# n.net
KiCad netlist of a schematic drawn in EAGLE
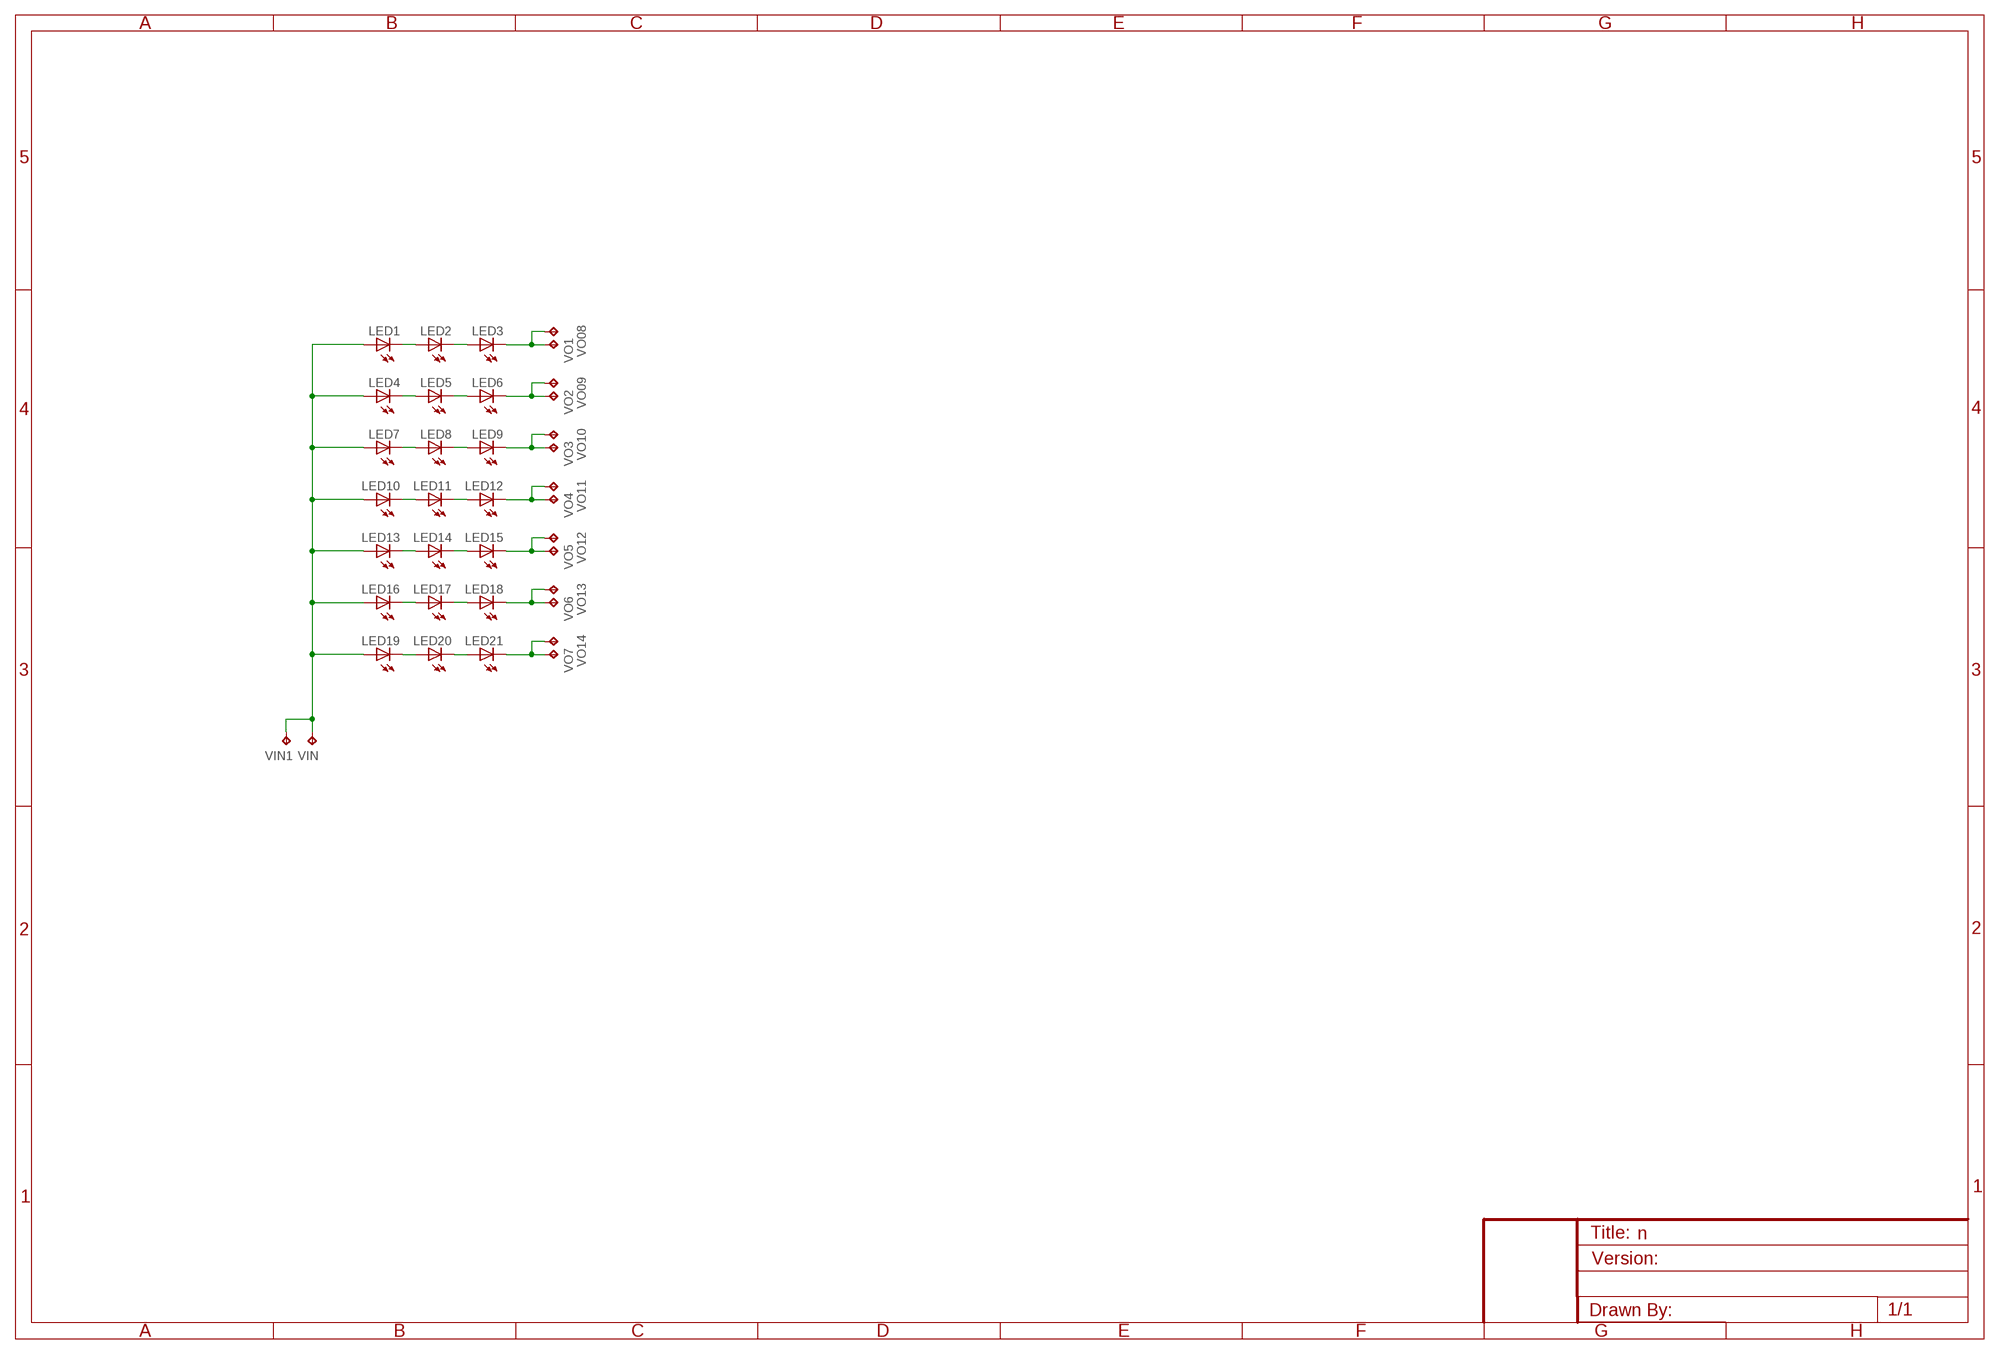
[diagram p0: schematic, sheet 1]

(export (version "E")
  (design (tool "Eeschema 10.0.6"))
  (components
    (comp (ref "LED1")
      (value "LED0805")
      (footprint "eagle-import:LED_0805")
      (libsource (lib "eagle-import") (part "LED0805"))
    )
    (comp (ref "LED2")
      (value "LED0805")
      (footprint "eagle-import:LED_0805")
      (libsource (lib "eagle-import") (part "LED0805"))
    )
    (comp (ref "LED3")
      (value "LED0805")
      (footprint "eagle-import:LED_0805")
      (libsource (lib "eagle-import") (part "LED0805"))
    )
    (comp (ref "LED4")
      (value "LED0805")
      (footprint "eagle-import:LED_0805")
      (libsource (lib "eagle-import") (part "LED0805"))
    )
    (comp (ref "LED5")
      (value "LED0805")
      (footprint "eagle-import:LED_0805")
      (libsource (lib "eagle-import") (part "LED0805"))
    )
    (comp (ref "LED6")
      (value "LED0805")
      (footprint "eagle-import:LED_0805")
      (libsource (lib "eagle-import") (part "LED0805"))
    )
    (comp (ref "LED7")
      (value "LED0805")
      (footprint "eagle-import:LED_0805")
      (libsource (lib "eagle-import") (part "LED0805"))
    )
    (comp (ref "LED8")
      (value "LED0805")
      (footprint "eagle-import:LED_0805")
      (libsource (lib "eagle-import") (part "LED0805"))
    )
    (comp (ref "LED9")
      (value "LED0805")
      (footprint "eagle-import:LED_0805")
      (libsource (lib "eagle-import") (part "LED0805"))
    )
    (comp (ref "LED10")
      (value "LED0805")
      (footprint "eagle-import:LED_0805")
      (libsource (lib "eagle-import") (part "LED0805"))
    )
    (comp (ref "LED11")
      (value "LED0805")
      (footprint "eagle-import:LED_0805")
      (libsource (lib "eagle-import") (part "LED0805"))
    )
    (comp (ref "LED12")
      (value "LED0805")
      (footprint "eagle-import:LED_0805")
      (libsource (lib "eagle-import") (part "LED0805"))
    )
    (comp (ref "LED13")
      (value "LED0805")
      (footprint "eagle-import:LED_0805")
      (libsource (lib "eagle-import") (part "LED0805"))
    )
    (comp (ref "LED14")
      (value "LED0805")
      (footprint "eagle-import:LED_0805")
      (libsource (lib "eagle-import") (part "LED0805"))
    )
    (comp (ref "LED15")
      (value "LED0805")
      (footprint "eagle-import:LED_0805")
      (libsource (lib "eagle-import") (part "LED0805"))
    )
    (comp (ref "LED16")
      (value "LED0805")
      (footprint "eagle-import:LED_0805")
      (libsource (lib "eagle-import") (part "LED0805"))
    )
    (comp (ref "LED17")
      (value "LED0805")
      (footprint "eagle-import:LED_0805")
      (libsource (lib "eagle-import") (part "LED0805"))
    )
    (comp (ref "LED18")
      (value "LED0805")
      (footprint "eagle-import:LED_0805")
      (libsource (lib "eagle-import") (part "LED0805"))
    )
    (comp (ref "LED19")
      (value "LED0805")
      (footprint "eagle-import:LED_0805")
      (libsource (lib "eagle-import") (part "LED0805"))
    )
    (comp (ref "LED20")
      (value "LED0805")
      (footprint "eagle-import:LED_0805")
      (libsource (lib "eagle-import") (part "LED0805"))
    )
    (comp (ref "LED21")
      (value "LED0805")
      (footprint "eagle-import:LED_0805")
      (libsource (lib "eagle-import") (part "LED0805"))
    )
    (comp (ref "VIN")
      (value "TEST_POINTPAD1-20")
      (footprint "eagle-import:P1-20")
      (libsource (lib "eagle-import") (part "TEST_POINTPAD1-20"))
    )
    (comp (ref "VIN1")
      (value "TEST_POINTPAD1-20")
      (footprint "eagle-import:P1-20")
      (libsource (lib "eagle-import") (part "TEST_POINTPAD1-20"))
    )
    (comp (ref "VO1")
      (value "TEST_POINTPAD1-20")
      (footprint "eagle-import:P1-20")
      (libsource (lib "eagle-import") (part "TEST_POINTPAD1-20"))
    )
    (comp (ref "VO2")
      (value "TEST_POINTPAD1-20")
      (footprint "eagle-import:P1-20")
      (libsource (lib "eagle-import") (part "TEST_POINTPAD1-20"))
    )
    (comp (ref "VO3")
      (value "TEST_POINTPAD1-20")
      (footprint "eagle-import:P1-20")
      (libsource (lib "eagle-import") (part "TEST_POINTPAD1-20"))
    )
    (comp (ref "VO4")
      (value "TEST_POINTPAD1-20")
      (footprint "eagle-import:P1-20")
      (libsource (lib "eagle-import") (part "TEST_POINTPAD1-20"))
    )
    (comp (ref "VO5")
      (value "TEST_POINTPAD1-20")
      (footprint "eagle-import:P1-20")
      (libsource (lib "eagle-import") (part "TEST_POINTPAD1-20"))
    )
    (comp (ref "VO6")
      (value "TEST_POINTPAD1-20")
      (footprint "eagle-import:P1-20")
      (libsource (lib "eagle-import") (part "TEST_POINTPAD1-20"))
    )
    (comp (ref "VO7")
      (value "TEST_POINTPAD1-20")
      (footprint "eagle-import:P1-20")
      (libsource (lib "eagle-import") (part "TEST_POINTPAD1-20"))
    )
    (comp (ref "VO08")
      (value "TEST_POINTPAD1-20")
      (footprint "eagle-import:P1-20")
      (libsource (lib "eagle-import") (part "TEST_POINTPAD1-20"))
    )
    (comp (ref "VO09")
      (value "TEST_POINTPAD1-20")
      (footprint "eagle-import:P1-20")
      (libsource (lib "eagle-import") (part "TEST_POINTPAD1-20"))
    )
    (comp (ref "VO10")
      (value "TEST_POINTPAD1-20")
      (footprint "eagle-import:P1-20")
      (libsource (lib "eagle-import") (part "TEST_POINTPAD1-20"))
    )
    (comp (ref "VO11")
      (value "TEST_POINTPAD1-20")
      (footprint "eagle-import:P1-20")
      (libsource (lib "eagle-import") (part "TEST_POINTPAD1-20"))
    )
    (comp (ref "VO12")
      (value "TEST_POINTPAD1-20")
      (footprint "eagle-import:P1-20")
      (libsource (lib "eagle-import") (part "TEST_POINTPAD1-20"))
    )
    (comp (ref "VO13")
      (value "TEST_POINTPAD1-20")
      (footprint "eagle-import:P1-20")
      (libsource (lib "eagle-import") (part "TEST_POINTPAD1-20"))
    )
    (comp (ref "VO14")
      (value "TEST_POINTPAD1-20")
      (footprint "eagle-import:P1-20")
      (libsource (lib "eagle-import") (part "TEST_POINTPAD1-20"))
    )
  )
  (nets
    (net (code "1") (name "Net-(LED1-PadA)") (class "Default")
      (node (ref "LED1") (pin "A") (pinfunction "A_A") (pintype "passive"))
      (node (ref "LED10") (pin "A") (pinfunction "A_A") (pintype "passive"))
      (node (ref "LED13") (pin "A") (pinfunction "A_A") (pintype "passive"))
      (node (ref "LED16") (pin "A") (pinfunction "A_A") (pintype "passive"))
      (node (ref "LED19") (pin "A") (pinfunction "A_A") (pintype "passive"))
      (node (ref "LED4") (pin "A") (pinfunction "A_A") (pintype "passive"))
      (node (ref "LED7") (pin "A") (pinfunction "A_A") (pintype "passive"))
      (node (ref "VIN") (pin "TP") (pinfunction "TP_TP") (pintype "input"))
      (node (ref "VIN1") (pin "TP") (pinfunction "TP_TP") (pintype "input"))
    )
    (net (code "2") (name "Net-(LED1-PadC)") (class "Default")
      (node (ref "LED1") (pin "C") (pinfunction "C_C") (pintype "passive"))
      (node (ref "LED2") (pin "A") (pinfunction "A_A") (pintype "passive"))
    )
    (net (code "3") (name "Net-(LED2-PadC)") (class "Default")
      (node (ref "LED2") (pin "C") (pinfunction "C_C") (pintype "passive"))
      (node (ref "LED3") (pin "A") (pinfunction "A_A") (pintype "passive"))
    )
    (net (code "4") (name "Net-(LED3-PadC)") (class "Default")
      (node (ref "LED3") (pin "C") (pinfunction "C_C") (pintype "passive"))
      (node (ref "VO08") (pin "TP") (pinfunction "TP_TP") (pintype "input"))
      (node (ref "VO1") (pin "TP") (pinfunction "TP_TP") (pintype "input"))
    )
    (net (code "5") (name "Net-(LED4-PadC)") (class "Default")
      (node (ref "LED4") (pin "C") (pinfunction "C_C") (pintype "passive"))
      (node (ref "LED5") (pin "A") (pinfunction "A_A") (pintype "passive"))
    )
    (net (code "6") (name "Net-(LED5-PadC)") (class "Default")
      (node (ref "LED5") (pin "C") (pinfunction "C_C") (pintype "passive"))
      (node (ref "LED6") (pin "A") (pinfunction "A_A") (pintype "passive"))
    )
    (net (code "7") (name "Net-(LED6-PadC)") (class "Default")
      (node (ref "LED6") (pin "C") (pinfunction "C_C") (pintype "passive"))
      (node (ref "VO09") (pin "TP") (pinfunction "TP_TP") (pintype "input"))
      (node (ref "VO2") (pin "TP") (pinfunction "TP_TP") (pintype "input"))
    )
    (net (code "8") (name "Net-(LED7-PadC)") (class "Default")
      (node (ref "LED7") (pin "C") (pinfunction "C_C") (pintype "passive"))
      (node (ref "LED8") (pin "A") (pinfunction "A_A") (pintype "passive"))
    )
    (net (code "9") (name "Net-(LED8-PadC)") (class "Default")
      (node (ref "LED8") (pin "C") (pinfunction "C_C") (pintype "passive"))
      (node (ref "LED9") (pin "A") (pinfunction "A_A") (pintype "passive"))
    )
    (net (code "10") (name "Net-(LED9-PadC)") (class "Default")
      (node (ref "LED9") (pin "C") (pinfunction "C_C") (pintype "passive"))
      (node (ref "VO10") (pin "TP") (pinfunction "TP_TP") (pintype "input"))
      (node (ref "VO3") (pin "TP") (pinfunction "TP_TP") (pintype "input"))
    )
    (net (code "11") (name "Net-(LED10-PadC)") (class "Default")
      (node (ref "LED10") (pin "C") (pinfunction "C_C") (pintype "passive"))
      (node (ref "LED11") (pin "A") (pinfunction "A_A") (pintype "passive"))
    )
    (net (code "12") (name "Net-(LED11-PadC)") (class "Default")
      (node (ref "LED11") (pin "C") (pinfunction "C_C") (pintype "passive"))
      (node (ref "LED12") (pin "A") (pinfunction "A_A") (pintype "passive"))
    )
    (net (code "13") (name "Net-(LED12-PadC)") (class "Default")
      (node (ref "LED12") (pin "C") (pinfunction "C_C") (pintype "passive"))
      (node (ref "VO11") (pin "TP") (pinfunction "TP_TP") (pintype "input"))
      (node (ref "VO4") (pin "TP") (pinfunction "TP_TP") (pintype "input"))
    )
    (net (code "14") (name "Net-(LED13-PadC)") (class "Default")
      (node (ref "LED13") (pin "C") (pinfunction "C_C") (pintype "passive"))
      (node (ref "LED14") (pin "A") (pinfunction "A_A") (pintype "passive"))
    )
    (net (code "15") (name "Net-(LED14-PadC)") (class "Default")
      (node (ref "LED14") (pin "C") (pinfunction "C_C") (pintype "passive"))
      (node (ref "LED15") (pin "A") (pinfunction "A_A") (pintype "passive"))
    )
    (net (code "16") (name "Net-(LED15-PadC)") (class "Default")
      (node (ref "LED15") (pin "C") (pinfunction "C_C") (pintype "passive"))
      (node (ref "VO12") (pin "TP") (pinfunction "TP_TP") (pintype "input"))
      (node (ref "VO5") (pin "TP") (pinfunction "TP_TP") (pintype "input"))
    )
    (net (code "17") (name "Net-(LED16-PadC)") (class "Default")
      (node (ref "LED16") (pin "C") (pinfunction "C_C") (pintype "passive"))
      (node (ref "LED17") (pin "A") (pinfunction "A_A") (pintype "passive"))
    )
    (net (code "18") (name "Net-(LED17-PadC)") (class "Default")
      (node (ref "LED17") (pin "C") (pinfunction "C_C") (pintype "passive"))
      (node (ref "LED18") (pin "A") (pinfunction "A_A") (pintype "passive"))
    )
    (net (code "19") (name "Net-(LED18-PadC)") (class "Default")
      (node (ref "LED18") (pin "C") (pinfunction "C_C") (pintype "passive"))
      (node (ref "VO13") (pin "TP") (pinfunction "TP_TP") (pintype "input"))
      (node (ref "VO6") (pin "TP") (pinfunction "TP_TP") (pintype "input"))
    )
    (net (code "20") (name "Net-(LED19-PadC)") (class "Default")
      (node (ref "LED19") (pin "C") (pinfunction "C_C") (pintype "passive"))
      (node (ref "LED20") (pin "A") (pinfunction "A_A") (pintype "passive"))
    )
    (net (code "21") (name "Net-(LED20-PadC)") (class "Default")
      (node (ref "LED20") (pin "C") (pinfunction "C_C") (pintype "passive"))
      (node (ref "LED21") (pin "A") (pinfunction "A_A") (pintype "passive"))
    )
    (net (code "22") (name "Net-(LED21-PadC)") (class "Default")
      (node (ref "LED21") (pin "C") (pinfunction "C_C") (pintype "passive"))
      (node (ref "VO14") (pin "TP") (pinfunction "TP_TP") (pintype "input"))
      (node (ref "VO7") (pin "TP") (pinfunction "TP_TP") (pintype "input"))
    )
  )
)
